# Project_Nixie.net
KiCad netlist of a schematic drawn in EAGLE
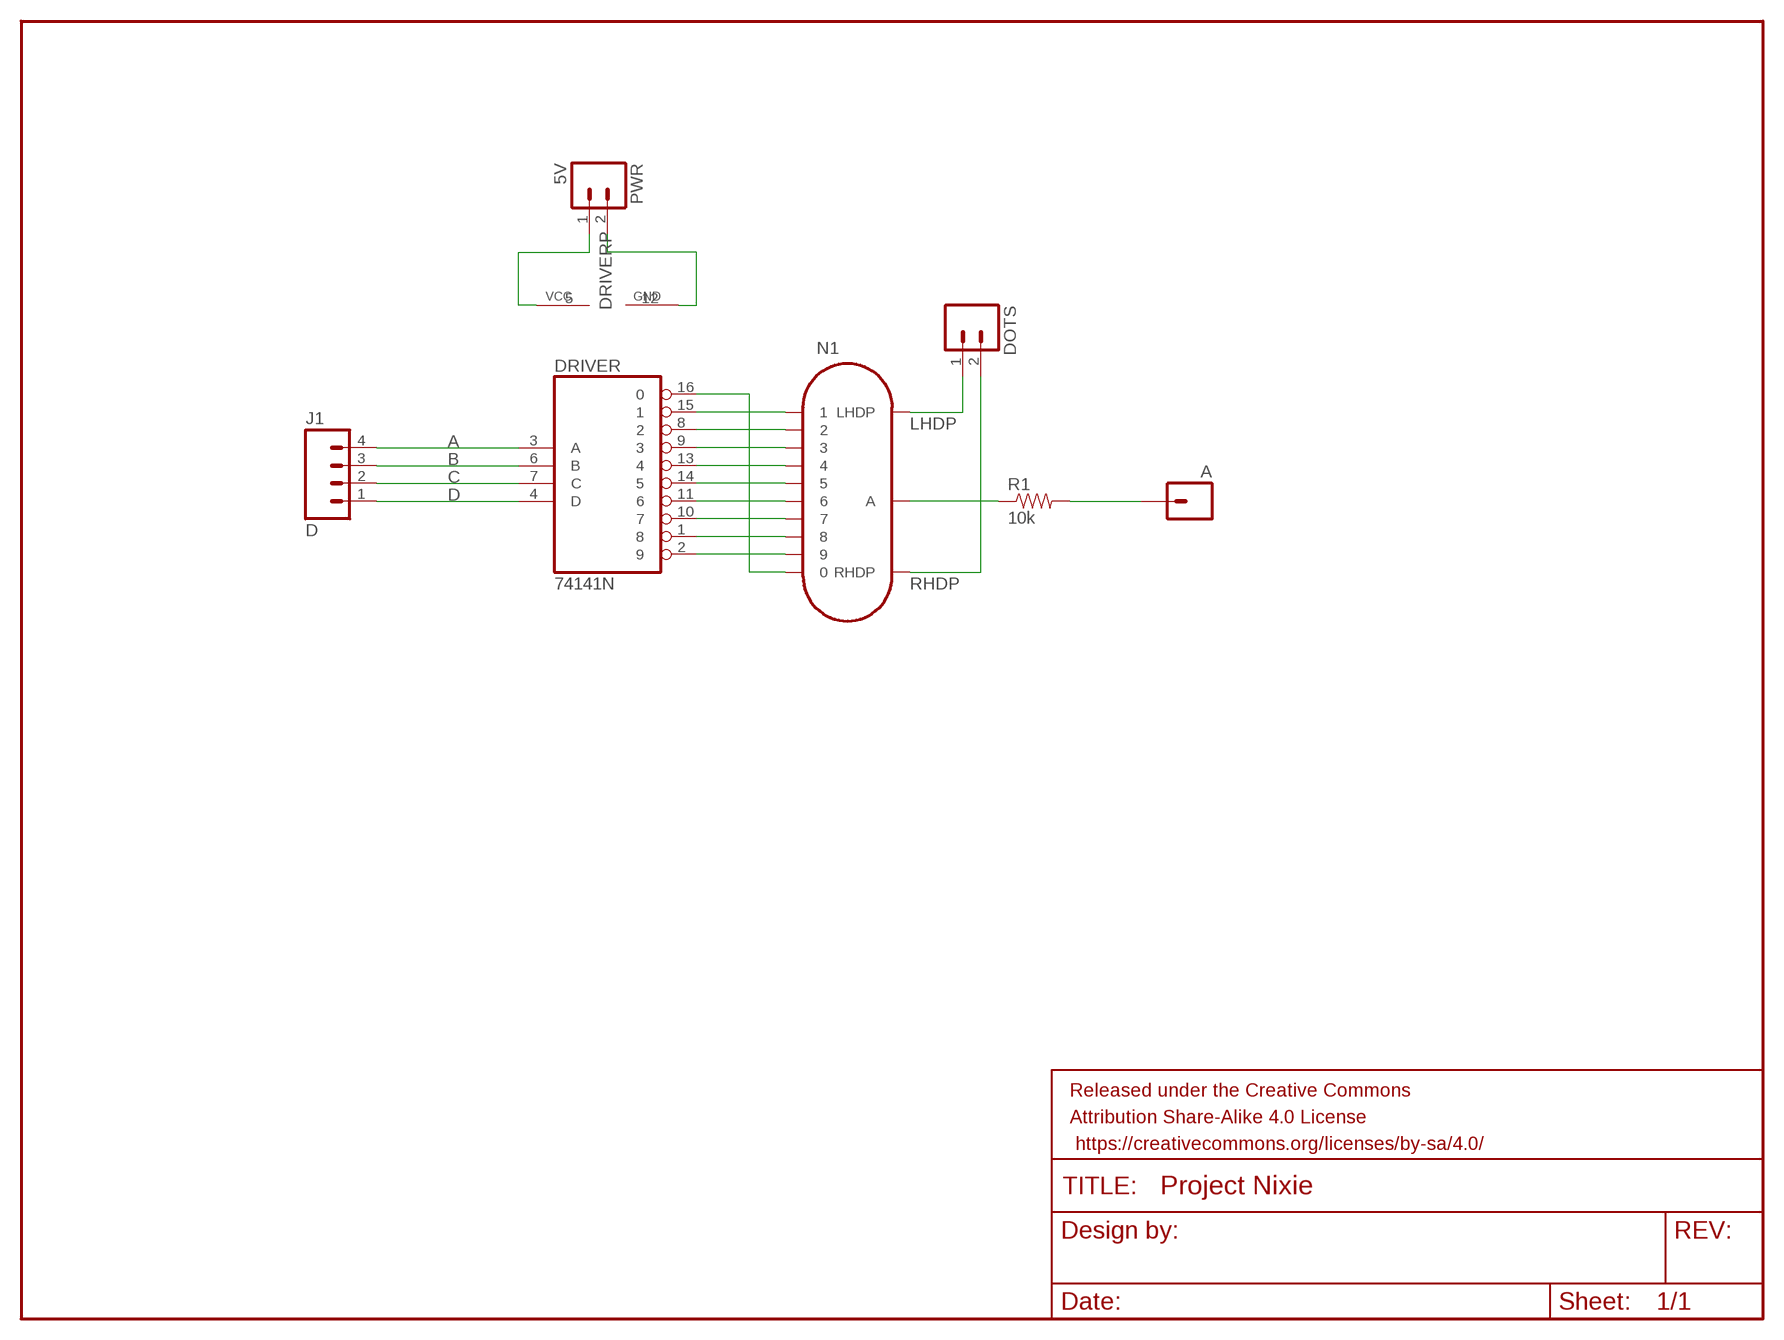
[diagram p0: schematic, sheet 1]

(export (version "E")
  (design (tool "Eeschema 10.0.6"))
  (components
    (comp (ref "A")
      (value "M01PTH")
      (footprint "eagle-import:1X01")
      (libsource (lib "eagle-import") (part "M01PTH"))
    )
    (comp (ref "DOTS")
      (value "M02PTH")
      (footprint "eagle-import:1X02")
      (libsource (lib "eagle-import") (part "M02PTH"))
    )
    (comp (ref "DRIVER")
      (value "74141N")
      (footprint "eagle-import:DIL16")
      (libsource (lib "eagle-import") (part "74141N"))
    )
    (comp (ref "FRAME1")
      (value "FRAME-LETTER")
      (footprint "eagle-import:CREATIVE_COMMONS")
      (libsource (lib "eagle-import") (part "FRAME-LETTER"))
    )
    (comp (ref "J1")
      (value "D")
      (footprint "eagle-import:1X04_LOCK")
      (libsource (lib "eagle-import") (part "M04LOCK"))
    )
    (comp (ref "N1")
      (value "IN-16")
      (footprint "eagle-import:IN-16")
      (libsource (lib "eagle-import") (part "IN-16"))
    )
    (comp (ref "PWR")
      (value "5V")
      (footprint "eagle-import:1X02_LOCK")
      (libsource (lib "eagle-import") (part "M02LOCK"))
    )
    (comp (ref "R1")
      (value "10k")
      (footprint "eagle-import:AXIAL-0.3")
      (libsource (lib "eagle-import") (part "RESISTORAXIAL-0.3"))
    )
  )
  (nets
    (net (code "1") (name "/A") (class "Default")
      (node (ref "DRIVER") (pin "3") (pinfunction "A_3") (pintype "input"))
      (node (ref "J1") (pin "4") (pinfunction "4_4") (pintype "passive"))
    )
    (net (code "2") (name "/B") (class "Default")
      (node (ref "DRIVER") (pin "6") (pinfunction "B_6") (pintype "input"))
      (node (ref "J1") (pin "3") (pinfunction "3_3") (pintype "passive"))
    )
    (net (code "3") (name "/C") (class "Default")
      (node (ref "DRIVER") (pin "7") (pinfunction "C_7") (pintype "input"))
      (node (ref "J1") (pin "2") (pinfunction "2_2") (pintype "passive"))
    )
    (net (code "4") (name "/D") (class "Default")
      (node (ref "DRIVER") (pin "4") (pinfunction "D_4") (pintype "input"))
      (node (ref "J1") (pin "1") (pinfunction "1_1") (pintype "passive"))
    )
    (net (code "5") (name "/LHDP") (class "Default")
      (node (ref "DOTS") (pin "1") (pinfunction "1_1") (pintype "passive"))
      (node (ref "N1") (pin "LHDP") (pinfunction "LHDP_LHDP") (pintype "bidirectional"))
    )
    (net (code "6") (name "/RHDP") (class "Default")
      (node (ref "DOTS") (pin "2") (pinfunction "2_2") (pintype "passive"))
      (node (ref "N1") (pin "RHDP") (pinfunction "RHDP_RHDP") (pintype "bidirectional"))
    )
    (net (code "7") (name "Net-(DRIVERA-0)") (class "Default")
      (node (ref "DRIVER") (pin "16") (pinfunction "0_16") (pintype "open_collector"))
      (node (ref "N1") (pin "0") (pinfunction "0_0") (pintype "bidirectional"))
    )
    (net (code "8") (name "Net-(DRIVERA-1)") (class "Default")
      (node (ref "DRIVER") (pin "15") (pinfunction "1_15") (pintype "open_collector"))
      (node (ref "N1") (pin "1") (pinfunction "1_1") (pintype "bidirectional"))
    )
    (net (code "9") (name "Net-(DRIVERA-2)") (class "Default")
      (node (ref "DRIVER") (pin "8") (pinfunction "2_8") (pintype "open_collector"))
      (node (ref "N1") (pin "2") (pinfunction "2_2") (pintype "bidirectional"))
    )
    (net (code "10") (name "Net-(DRIVERA-3)") (class "Default")
      (node (ref "DRIVER") (pin "9") (pinfunction "3_9") (pintype "open_collector"))
      (node (ref "N1") (pin "3") (pinfunction "3_3") (pintype "bidirectional"))
    )
    (net (code "11") (name "Net-(DRIVERA-4)") (class "Default")
      (node (ref "DRIVER") (pin "13") (pinfunction "4_13") (pintype "open_collector"))
      (node (ref "N1") (pin "4") (pinfunction "4_4") (pintype "bidirectional"))
    )
    (net (code "12") (name "Net-(DRIVERA-5)") (class "Default")
      (node (ref "DRIVER") (pin "14") (pinfunction "5_14") (pintype "open_collector"))
      (node (ref "N1") (pin "5") (pinfunction "5_5") (pintype "bidirectional"))
    )
    (net (code "13") (name "Net-(DRIVERA-6)") (class "Default")
      (node (ref "DRIVER") (pin "11") (pinfunction "6_11") (pintype "open_collector"))
      (node (ref "N1") (pin "6") (pinfunction "6_6") (pintype "bidirectional"))
    )
    (net (code "14") (name "Net-(DRIVERA-7)") (class "Default")
      (node (ref "DRIVER") (pin "10") (pinfunction "7_10") (pintype "open_collector"))
      (node (ref "N1") (pin "7") (pinfunction "7_7") (pintype "bidirectional"))
    )
    (net (code "15") (name "Net-(DRIVERA-8)") (class "Default")
      (node (ref "DRIVER") (pin "1") (pinfunction "8_1") (pintype "open_collector"))
      (node (ref "N1") (pin "8") (pinfunction "8_8") (pintype "bidirectional"))
    )
    (net (code "16") (name "Net-(DRIVERA-9)") (class "Default")
      (node (ref "DRIVER") (pin "2") (pinfunction "9_2") (pintype "open_collector"))
      (node (ref "N1") (pin "9") (pinfunction "9_9") (pintype "bidirectional"))
    )
    (net (code "17") (name "Net-(DRIVERB-GND)") (class "Default")
      (node (ref "DRIVER") (pin "12") (pinfunction "GND_12") (pintype "power_in"))
      (node (ref "PWR") (pin "2") (pinfunction "2_2") (pintype "passive"))
    )
    (net (code "18") (name "Net-(DRIVERB-VCC)") (class "Default")
      (node (ref "DRIVER") (pin "5") (pinfunction "VCC_5") (pintype "power_in"))
      (node (ref "PWR") (pin "1") (pinfunction "1_1") (pintype "passive"))
    )
    (net (code "19") (name "Net-(R1-1)") (class "Default")
      (node (ref "N1") (pin "A") (pinfunction "A_A") (pintype "bidirectional"))
      (node (ref "R1") (pin "P$1") (pinfunction "1_P$1") (pintype "passive"))
    )
    (net (code "20") (name "Net-(R1-2)") (class "Default")
      (node (ref "A") (pin "1") (pinfunction "1_1") (pintype "passive"))
      (node (ref "R1") (pin "P$2") (pinfunction "2_P$2") (pintype "passive"))
    )
  )
)
